# BeagleBoard-Fluxos.net
KiCad netlist of a schematic drawn in EAGLE
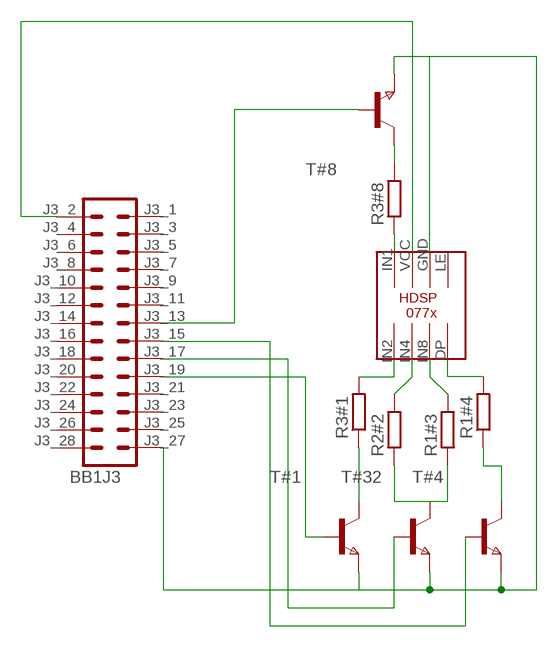
[diagram p0: schematic, sheet 1]

(export (version "E")
  (design (tool "Eeschema 10.0.6"))
  (components
    (comp (ref "BB1")
      (value "BEAGLE_EXPANSION")
      (footprint "eagle-import:BEAGLE_EXPANSION")
      (libsource (lib "eagle-import") (part "BEAGLE_EXPANSION"))
    )
    (comp (ref "R1#3")
      (value "R-EU_0309/12")
      (footprint "eagle-import:0309_12")
      (libsource (lib "eagle-import") (part "R-EU_0309/12"))
    )
    (comp (ref "R1#4")
      (value "R-EU_0309/12")
      (footprint "eagle-import:0309_12")
      (libsource (lib "eagle-import") (part "R-EU_0309/12"))
    )
    (comp (ref "R2#2")
      (value "R-EU_0309/12")
      (footprint "eagle-import:0309_12")
      (libsource (lib "eagle-import") (part "R-EU_0309/12"))
    )
    (comp (ref "R3#1")
      (value "R-EU_0309/12")
      (footprint "eagle-import:0309_12")
      (libsource (lib "eagle-import") (part "R-EU_0309/12"))
    )
    (comp (ref "R3#8")
      (value "R-EU_0309/12")
      (footprint "eagle-import:0309_12")
      (libsource (lib "eagle-import") (part "R-EU_0309/12"))
    )
    (comp (ref "T#1")
      (value "NPNSOT323")
      (footprint "eagle-import:SOT323")
      (fields (field (name "MPN") "DSS4160U-7"))
      (libsource (lib "eagle-import") (part "NPNSOT323"))
    )
    (comp (ref "T#4")
      (value "NPNSOT323")
      (footprint "eagle-import:SOT323")
      (fields (field (name "MPN") "DSS4160U-7"))
      (libsource (lib "eagle-import") (part "NPNSOT323"))
    )
    (comp (ref "T#8")
      (value "NPNSOT323")
      (footprint "eagle-import:SOT323")
      (fields (field (name "MPN") "DSS4160U-7"))
      (libsource (lib "eagle-import") (part "NPNSOT323"))
    )
    (comp (ref "T#32")
      (value "NPNSOT323")
      (footprint "eagle-import:SOT323")
      (fields (field (name "MPN") "DSS4160U-7"))
      (libsource (lib "eagle-import") (part "NPNSOT323"))
    )
    (comp (ref "U$1")
      (value "HDSP-077X")
      (footprint "eagle-import:HDSP-077X")
      (libsource (lib "eagle-import") (part "HDSP-077X"))
    )
  )
  (nets
    (net (code "1") (name "Net-(BB1A-2)") (class "Default")
      (node (ref "BB1") (pin "J3_2") (pinfunction "2_J3_2") (pintype "passive"))
      (node (ref "U$1") (pin "VCC") (pinfunction "VCC_VCC") (pintype "bidirectional"))
    )
    (net (code "2") (name "Net-(BB1A-13)") (class "Default")
      (node (ref "BB1") (pin "J3_13") (pinfunction "13_J3_13") (pintype "passive"))
      (node (ref "T#8") (pin "2") (pinfunction "B_2") (pintype "passive"))
    )
    (net (code "3") (name "Net-(BB1A-15)") (class "Default")
      (node (ref "BB1") (pin "J3_15") (pinfunction "15_J3_15") (pintype "passive"))
      (node (ref "T#4") (pin "2") (pinfunction "B_2") (pintype "passive"))
    )
    (net (code "4") (name "Net-(BB1A-17)") (class "Default")
      (node (ref "BB1") (pin "J3_17") (pinfunction "17_J3_17") (pintype "passive"))
      (node (ref "T#32") (pin "2") (pinfunction "B_2") (pintype "passive"))
    )
    (net (code "5") (name "Net-(BB1A-19)") (class "Default")
      (node (ref "BB1") (pin "J3_19") (pinfunction "19_J3_19") (pintype "passive"))
      (node (ref "T#1") (pin "2") (pinfunction "B_2") (pintype "passive"))
    )
    (net (code "6") (name "Net-(BB1A-27)") (class "Default")
      (node (ref "BB1") (pin "J3_27") (pinfunction "27_J3_27") (pintype "passive"))
      (node (ref "T#1") (pin "3") (pinfunction "E_3") (pintype "passive"))
      (node (ref "T#32") (pin "3") (pinfunction "E_3") (pintype "passive"))
      (node (ref "T#4") (pin "3") (pinfunction "E_3") (pintype "passive"))
      (node (ref "T#8") (pin "3") (pinfunction "E_3") (pintype "passive"))
      (node (ref "U$1") (pin "GND") (pinfunction "GND_GND") (pintype "bidirectional"))
    )
    (net (code "7") (name "Net-(R1#3-Pad2)") (class "Default")
      (node (ref "R1#3") (pin "2") (pinfunction "2_2") (pintype "passive"))
      (node (ref "U$1") (pin "IN8") (pinfunction "IN8_IN8") (pintype "bidirectional"))
    )
    (net (code "8") (name "Net-(R1#4-Pad2)") (class "Default")
      (node (ref "R1#4") (pin "2") (pinfunction "2_2") (pintype "passive"))
      (node (ref "U$1") (pin "DP") (pinfunction "DP_DP") (pintype "bidirectional"))
    )
    (net (code "9") (name "Net-(R2#2-Pad2)") (class "Default")
      (node (ref "R2#2") (pin "2") (pinfunction "2_2") (pintype "passive"))
      (node (ref "U$1") (pin "IN4") (pinfunction "IN4_IN4") (pintype "bidirectional"))
    )
    (net (code "10") (name "Net-(R3#1-Pad2)") (class "Default")
      (node (ref "R3#1") (pin "2") (pinfunction "2_2") (pintype "passive"))
      (node (ref "U$1") (pin "IN2") (pinfunction "IN2_IN2") (pintype "bidirectional"))
    )
    (net (code "11") (name "Net-(R3#8-Pad1)") (class "Default")
      (node (ref "R3#8") (pin "1") (pinfunction "1_1") (pintype "passive"))
      (node (ref "U$1") (pin "IN1") (pinfunction "IN1_IN1") (pintype "bidirectional"))
    )
    (net (code "12") (name "Net-(T#1-C)") (class "Default")
      (node (ref "R3#1") (pin "1") (pinfunction "1_1") (pintype "passive"))
      (node (ref "T#1") (pin "1") (pinfunction "C_1") (pintype "passive"))
    )
    (net (code "13") (name "Net-(T#4-C)") (class "Default")
      (node (ref "R1#4") (pin "1") (pinfunction "1_1") (pintype "passive"))
      (node (ref "T#4") (pin "1") (pinfunction "C_1") (pintype "passive"))
    )
    (net (code "14") (name "Net-(T#8-C)") (class "Default")
      (node (ref "R3#8") (pin "2") (pinfunction "2_2") (pintype "passive"))
      (node (ref "T#8") (pin "1") (pinfunction "C_1") (pintype "passive"))
    )
    (net (code "15") (name "Net-(T#32-C)") (class "Default")
      (node (ref "R1#3") (pin "1") (pinfunction "1_1") (pintype "passive"))
      (node (ref "R2#2") (pin "1") (pinfunction "1_1") (pintype "passive"))
      (node (ref "T#32") (pin "1") (pinfunction "C_1") (pintype "passive"))
    )
    (net (code "16") (name "unconnected-(BB1A-1-PadJ3_1)") (class "Default")
      (node (ref "BB1") (pin "J3_1") (pinfunction "1_J3_1") (pintype "passive"))
    )
    (net (code "17") (name "unconnected-(BB1A-3-PadJ3_3)") (class "Default")
      (node (ref "BB1") (pin "J3_3") (pinfunction "3_J3_3") (pintype "passive"))
    )
    (net (code "18") (name "unconnected-(BB1A-4-PadJ3_4)") (class "Default")
      (node (ref "BB1") (pin "J3_4") (pinfunction "4_J3_4") (pintype "passive"))
    )
    (net (code "19") (name "unconnected-(BB1A-5-PadJ3_5)") (class "Default")
      (node (ref "BB1") (pin "J3_5") (pinfunction "5_J3_5") (pintype "passive"))
    )
    (net (code "20") (name "unconnected-(BB1A-6-PadJ3_6)") (class "Default")
      (node (ref "BB1") (pin "J3_6") (pinfunction "6_J3_6") (pintype "passive"))
    )
    (net (code "21") (name "unconnected-(BB1A-7-PadJ3_7)") (class "Default")
      (node (ref "BB1") (pin "J3_7") (pinfunction "7_J3_7") (pintype "passive"))
    )
    (net (code "22") (name "unconnected-(BB1A-8-PadJ3_8)") (class "Default")
      (node (ref "BB1") (pin "J3_8") (pinfunction "8_J3_8") (pintype "passive"))
    )
    (net (code "23") (name "unconnected-(BB1A-9-PadJ3_9)") (class "Default")
      (node (ref "BB1") (pin "J3_9") (pinfunction "9_J3_9") (pintype "passive"))
    )
    (net (code "24") (name "unconnected-(BB1A-10-PadJ3_10)") (class "Default")
      (node (ref "BB1") (pin "J3_10") (pinfunction "10_J3_10") (pintype "passive"))
    )
    (net (code "25") (name "unconnected-(BB1A-11-PadJ3_11)") (class "Default")
      (node (ref "BB1") (pin "J3_11") (pinfunction "11_J3_11") (pintype "passive"))
    )
    (net (code "26") (name "unconnected-(BB1A-12-PadJ3_12)") (class "Default")
      (node (ref "BB1") (pin "J3_12") (pinfunction "12_J3_12") (pintype "passive"))
    )
    (net (code "27") (name "unconnected-(BB1A-14-PadJ3_14)") (class "Default")
      (node (ref "BB1") (pin "J3_14") (pinfunction "14_J3_14") (pintype "passive"))
    )
    (net (code "28") (name "unconnected-(BB1A-16-PadJ3_16)") (class "Default")
      (node (ref "BB1") (pin "J3_16") (pinfunction "16_J3_16") (pintype "passive"))
    )
    (net (code "29") (name "unconnected-(BB1A-18-PadJ3_18)") (class "Default")
      (node (ref "BB1") (pin "J3_18") (pinfunction "18_J3_18") (pintype "passive"))
    )
    (net (code "30") (name "unconnected-(BB1A-20-PadJ3_20)") (class "Default")
      (node (ref "BB1") (pin "J3_20") (pinfunction "20_J3_20") (pintype "passive"))
    )
    (net (code "31") (name "unconnected-(BB1A-21-PadJ3_21)") (class "Default")
      (node (ref "BB1") (pin "J3_21") (pinfunction "21_J3_21") (pintype "passive"))
    )
    (net (code "32") (name "unconnected-(BB1A-22-PadJ3_22)") (class "Default")
      (node (ref "BB1") (pin "J3_22") (pinfunction "22_J3_22") (pintype "passive"))
    )
    (net (code "33") (name "unconnected-(BB1A-23-PadJ3_23)") (class "Default")
      (node (ref "BB1") (pin "J3_23") (pinfunction "23_J3_23") (pintype "passive"))
    )
    (net (code "34") (name "unconnected-(BB1A-24-PadJ3_24)") (class "Default")
      (node (ref "BB1") (pin "J3_24") (pinfunction "24_J3_24") (pintype "passive"))
    )
    (net (code "35") (name "unconnected-(BB1A-25-PadJ3_25)") (class "Default")
      (node (ref "BB1") (pin "J3_25") (pinfunction "25_J3_25") (pintype "passive"))
    )
    (net (code "36") (name "unconnected-(BB1A-26-PadJ3_26)") (class "Default")
      (node (ref "BB1") (pin "J3_26") (pinfunction "26_J3_26") (pintype "passive"))
    )
    (net (code "37") (name "unconnected-(BB1A-28-PadJ3_28)") (class "Default")
      (node (ref "BB1") (pin "J3_28") (pinfunction "28_J3_28") (pintype "passive"))
    )
    (net (code "38") (name "unconnected-(U$1-PadLE)") (class "Default")
      (node (ref "U$1") (pin "LE") (pinfunction "LE_LE") (pintype "bidirectional"))
    )
  )
)
